# V1_pwr_sply_noNegSply_sch.net
KiCad netlist of a schematic drawn in Altium Designer
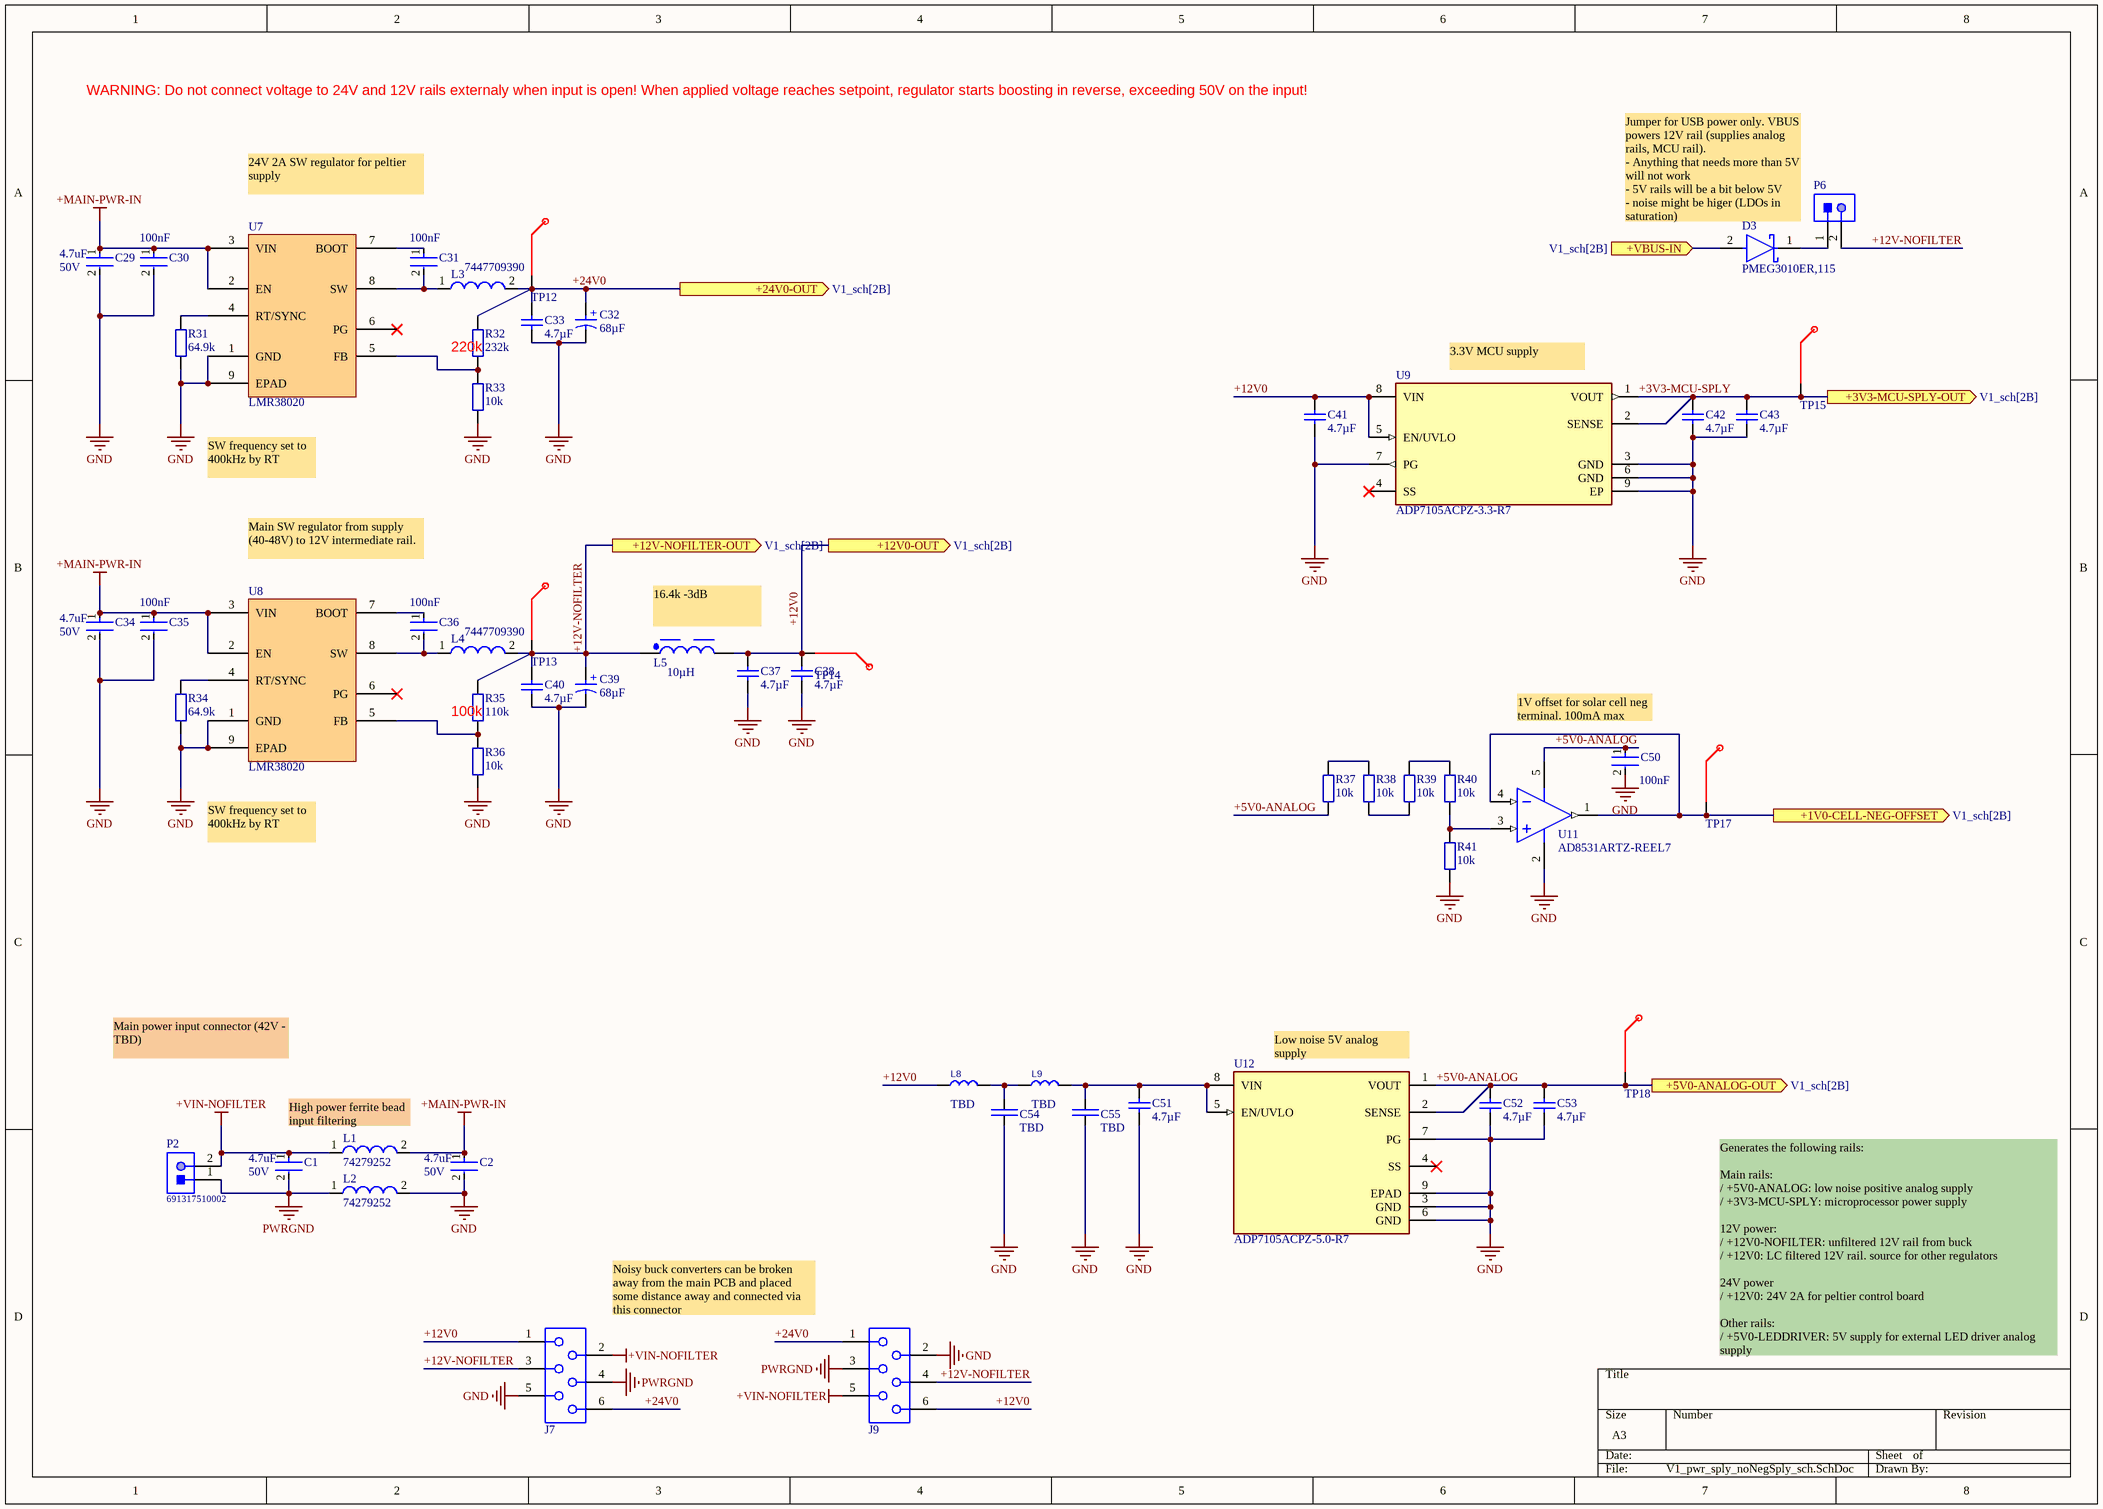
[diagram p0: V1_pwr_sply_noNegSply_sch.SchDoc]

(export (version "E")
  (design (tool "Eeschema 10.0.6"))
  (components
    (comp (ref "C1")
      (value "885012208094")
      (footprint "FP-885012208094-IPC_B")
      (description "CAP CER 4.7UF 50V X7R 1206")
      (fields
        (field (name "VOLTAGE RATING (DC)") "50V")
        (field (name "CAPACITANCE") "4.7uF")
        (field (name "TOLERANCE") "10%")
      )
      (libsource (lib "Altium Content Vault") (part "11868f565c42a9108669ba33697ecf6"))
    )
    (comp (ref "C2")
      (value "885012208094")
      (footprint "FP-885012208094-IPC_B")
      (description "CAP CER 4.7UF 50V X7R 1206")
      (fields
        (field (name "VOLTAGE RATING (DC)") "50V")
        (field (name "CAPACITANCE") "4.7uF")
        (field (name "TOLERANCE") "10%")
      )
      (libsource (lib "Altium Content Vault") (part "11868f565c42a9108669ba33697ecf6"))
    )
    (comp (ref "C29")
      (value "885012208094")
      (footprint "FP-885012208094-IPC_B")
      (description "CAP CER 4.7UF 50V X7R 1206")
      (fields
        (field (name "VOLTAGE RATING (DC)") "50V")
        (field (name "CAPACITANCE") "4.7uF")
        (field (name "TOLERANCE") "10%")
      )
      (libsource (lib "Altium Content Vault") (part "11868f565c42a9108669ba33697ecf6"))
    )
    (comp (ref "C30")
      (value "885012206095")
      (footprint "FP-885012206095-IPC_B")
      (description "CAP CER 0.1UF 50V X7R 0603")
      (fields (field (name "TOLERANCE") "10%") (field (name "CAPACITANCE") "100nF"))
      (libsource (lib "Altium Content Vault") (part "11868f565c42a9108669ba33697ecf6"))
    )
    (comp (ref "C31")
      (value "885012206095")
      (footprint "FP-885012206095-IPC_B")
      (description "CAP CER 0.1UF 50V X7R 0603")
      (fields (field (name "TOLERANCE") "10%") (field (name "CAPACITANCE") "100nF"))
      (libsource (lib "Altium Content Vault") (part "11868f565c42a9108669ba33697ecf6"))
    )
    (comp (ref "C32")
      (value "875115552001")
      (footprint "WCAP-PSHP_D8H8.7")
      (description "WCAP-PSHP Aluminum Polymer Capacitor, V-Chip, SMT, D8 x H8.7mm, 68µF, 25V")
      (fields (field (name "MANUFACTURER") "Wurth Elektronik") (field (name "CAPACITANCE") "68µF"))
      (libsource (lib "Altium_WCAP-PSHP (rev22c)") (part "875115552001"))
    )
    (comp (ref "C33")
      (value "885012107018")
      (footprint "WCAP-CSGP_0805_L2W1.25H1.25")
      (description "WCAP-CSGP Multilayer Ceramic Chip Capacitor, General Purpose, size 0805, X5R, 4.7µF, 25VDC")
      (fields (field (name "MANUFACTURER") "Wurth Elektronik") (field (name "CAPACITANCE") "4.7µF"))
      (libsource (lib "Altium_WCAP-CSGP (rev22f)") (part "885012107018"))
    )
    (comp (ref "C34")
      (value "885012208094")
      (footprint "FP-885012208094-IPC_B")
      (description "CAP CER 4.7UF 50V X7R 1206")
      (fields
        (field (name "VOLTAGE RATING (DC)") "50V")
        (field (name "CAPACITANCE") "4.7uF")
        (field (name "TOLERANCE") "10%")
      )
      (libsource (lib "Altium Content Vault") (part "11868f565c42a9108669ba33697ecf6"))
    )
    (comp (ref "C35")
      (value "885012206095")
      (footprint "FP-885012206095-IPC_B")
      (description "CAP CER 0.1UF 50V X7R 0603")
      (fields (field (name "TOLERANCE") "10%") (field (name "CAPACITANCE") "100nF"))
      (libsource (lib "Altium Content Vault") (part "11868f565c42a9108669ba33697ecf6"))
    )
    (comp (ref "C36")
      (value "885012206095")
      (footprint "FP-885012206095-IPC_B")
      (description "CAP CER 0.1UF 50V X7R 0603")
      (fields (field (name "TOLERANCE") "10%") (field (name "CAPACITANCE") "100nF"))
      (libsource (lib "Altium Content Vault") (part "11868f565c42a9108669ba33697ecf6"))
    )
    (comp (ref "C37")
      (value "885012107018")
      (footprint "WCAP-CSGP_0805_L2W1.25H1.25")
      (description "WCAP-CSGP Multilayer Ceramic Chip Capacitor, General Purpose, size 0805, X5R, 4.7µF, 25VDC")
      (fields (field (name "MANUFACTURER") "Wurth Elektronik") (field (name "CAPACITANCE") "4.7µF"))
      (libsource (lib "Altium_WCAP-CSGP (rev22f)") (part "885012107018"))
    )
    (comp (ref "C38")
      (value "885012107018")
      (footprint "WCAP-CSGP_0805_L2W1.25H1.25")
      (description "WCAP-CSGP Multilayer Ceramic Chip Capacitor, General Purpose, size 0805, X5R, 4.7µF, 25VDC")
      (fields (field (name "MANUFACTURER") "Wurth Elektronik") (field (name "CAPACITANCE") "4.7µF"))
      (libsource (lib "Altium_WCAP-CSGP (rev22f)") (part "885012107018"))
    )
    (comp (ref "C39")
      (value "875115552001")
      (footprint "WCAP-PSHP_D8H8.7")
      (description "WCAP-PSHP Aluminum Polymer Capacitor, V-Chip, SMT, D8 x H8.7mm, 68µF, 25V")
      (fields (field (name "MANUFACTURER") "Wurth Elektronik") (field (name "CAPACITANCE") "68µF"))
      (libsource (lib "Altium_WCAP-PSHP (rev22c)") (part "875115552001"))
    )
    (comp (ref "C40")
      (value "885012107018")
      (footprint "WCAP-CSGP_0805_L2W1.25H1.25")
      (description "WCAP-CSGP Multilayer Ceramic Chip Capacitor, General Purpose, size 0805, X5R, 4.7µF, 25VDC")
      (fields (field (name "MANUFACTURER") "Wurth Elektronik") (field (name "CAPACITANCE") "4.7µF"))
      (libsource (lib "Altium_WCAP-CSGP (rev22f)") (part "885012107018"))
    )
    (comp (ref "C41")
      (value "885012107018")
      (footprint "WCAP-CSGP_0805_L2W1.25H1.25")
      (description "WCAP-CSGP Multilayer Ceramic Chip Capacitor, General Purpose, size 0805, X5R, 4.7µF, 25VDC")
      (fields (field (name "MANUFACTURER") "Wurth Elektronik") (field (name "CAPACITANCE") "4.7µF"))
      (libsource (lib "Altium_WCAP-CSGP (rev22f)") (part "885012107018"))
    )
    (comp (ref "C42")
      (value "885012107018")
      (footprint "WCAP-CSGP_0805_L2W1.25H1.25")
      (description "WCAP-CSGP Multilayer Ceramic Chip Capacitor, General Purpose, size 0805, X5R, 4.7µF, 25VDC")
      (fields (field (name "MANUFACTURER") "Wurth Elektronik") (field (name "CAPACITANCE") "4.7µF"))
      (libsource (lib "Altium_WCAP-CSGP (rev22f)") (part "885012107018"))
    )
    (comp (ref "C43")
      (value "885012107018")
      (footprint "WCAP-CSGP_0805_L2W1.25H1.25")
      (description "WCAP-CSGP Multilayer Ceramic Chip Capacitor, General Purpose, size 0805, X5R, 4.7µF, 25VDC")
      (fields (field (name "MANUFACTURER") "Wurth Elektronik") (field (name "CAPACITANCE") "4.7µF"))
      (libsource (lib "Altium_WCAP-CSGP (rev22f)") (part "885012107018"))
    )
    (comp (ref "C50")
      (value "885012206095")
      (footprint "FP-885012206095-IPC_B")
      (description "CAP CER 0.1UF 50V X7R 0603")
      (fields (field (name "TOLERANCE") "10%") (field (name "CAPACITANCE") "100nF"))
      (libsource (lib "Altium Content Vault") (part "11868f565c42a9108669ba33697ecf6"))
    )
    (comp (ref "C51")
      (value "885012107018")
      (footprint "WCAP-CSGP_0805_L2W1.25H1.25")
      (description "WCAP-CSGP Multilayer Ceramic Chip Capacitor, General Purpose, size 0805, X5R, 4.7µF, 25VDC")
      (fields (field (name "MANUFACTURER") "Wurth Elektronik") (field (name "CAPACITANCE") "4.7µF"))
      (libsource (lib "Altium_WCAP-CSGP (rev22f)") (part "885012107018"))
    )
    (comp (ref "C52")
      (value "885012107018")
      (footprint "WCAP-CSGP_0805_L2W1.25H1.25")
      (description "WCAP-CSGP Multilayer Ceramic Chip Capacitor, General Purpose, size 0805, X5R, 4.7µF, 25VDC")
      (fields (field (name "MANUFACTURER") "Wurth Elektronik") (field (name "CAPACITANCE") "4.7µF"))
      (libsource (lib "Altium_WCAP-CSGP (rev22f)") (part "885012107018"))
    )
    (comp (ref "C53")
      (value "885012107018")
      (footprint "WCAP-CSGP_0805_L2W1.25H1.25")
      (description "WCAP-CSGP Multilayer Ceramic Chip Capacitor, General Purpose, size 0805, X5R, 4.7µF, 25VDC")
      (fields (field (name "MANUFACTURER") "Wurth Elektronik") (field (name "CAPACITANCE") "4.7µF"))
      (libsource (lib "Altium_WCAP-CSGP (rev22f)") (part "885012107018"))
    )
    (comp (ref "C54")
      (value "TBD")
      (footprint "Passives:FPR_0603_C_R0")
      (description "Capacitor - generic SMD")
      (fields (field (name "Comment") "PN_C0603_TBD"))
      (libsource (lib "Passives") (part "C"))
    )
    (comp (ref "C55")
      (value "TBD")
      (footprint "Passives:FPR_0603_C_R0")
      (description "Capacitor - generic SMD")
      (fields (field (name "Comment") "PN_C0603_TBD"))
      (libsource (lib "Passives") (part "C"))
    )
    (comp (ref "D3")
      (value "PMEG3010ER,115")
      (footprint "FP-SOD123W-MFG")
      (description "DIODE SCHOTTKY 30V 1A CFP3")
      (libsource (lib "Altium Content Vault") (part "1d6ec82d83fb6aee721767c19dac4b9"))
    )
    (comp (ref "J7")
      (value "690368190672")
      (footprint "690368190672")
      (description "WR-MM Mini Module Connector, Female, THT, with Latch & Polarization, Angled, pitch 2.54mm, 6p")
      (fields (field (name "MANUFACTURER") "Wurth Elektronik"))
      (libsource (lib "Altium_WR-MM (rev22a)") (part "690368190672"))
    )
    (comp (ref "J9")
      (value "690368190672")
      (footprint "690368190672")
      (description "WR-MM Mini Module Connector, Female, THT, with Latch & Polarization, Angled, pitch 2.54mm, 6p")
      (fields (field (name "MANUFACTURER") "Wurth Elektronik"))
      (libsource (lib "Altium_WR-MM (rev22a)") (part "690368190672"))
    )
    (comp (ref "L1")
      (value "74279252")
      (footprint "SMD-1812")
      (description "SMD EMI Suppression Ferrite Bead WE-CBF, Z = 680 Ohm")
      (libsource (lib "Altium Content Vault") (part "PAS-IND-INDUCTOR-2"))
    )
    (comp (ref "L2")
      (value "74279252")
      (footprint "SMD-1812")
      (description "SMD EMI Suppression Ferrite Bead WE-CBF, Z = 680 Ohm")
      (libsource (lib "Altium Content Vault") (part "PAS-IND-INDUCTOR-2"))
    )
    (comp (ref "L3")
      (value "7447709390")
      (footprint "WE-PD-XXL")
      (description "SMD-Shielded Power Inductor WE-PD, L = 39.0 µH")
      (libsource (lib "Altium Content Vault") (part "PAS-IND-INDUCTOR-2"))
    )
    (comp (ref "L4")
      (value "7447709390")
      (footprint "WE-PD-XXL")
      (description "SMD-Shielded Power Inductor WE-PD, L = 39.0 µH")
      (libsource (lib "Altium Content Vault") (part "PAS-IND-INDUCTOR-2"))
    )
    (comp (ref "L5")
      (value "74439346100")
      (footprint "WE-XHMI_6060_L6.65W6.45H5.8")
      (description "WE-XHMI SMT Power Inductor, size 6060, 10µH, 5A, 26.5mΩ")
      (fields (field (name "MANUFACTURER") "Wurth Elektronik") (field (name "INDUCTANCE") "10µH"))
      (libsource (lib "Altium_WE-XHMI (rev22e)") (part "74439346100"))
    )
    (comp (ref "L8")
      (value "TBD")
      (footprint "FPR_1216_R_R0")
      (description "Inductor - generic SMD")
      (fields (field (name "Comment") "L-TBD"))
      (libsource (lib "Passives") (part "L"))
    )
    (comp (ref "L9")
      (value "TBD")
      (footprint "FPR_1216_R_R0")
      (description "Inductor - generic SMD")
      (fields (field (name "Comment") "L-TBD"))
      (libsource (lib "Passives") (part "L"))
    )
    (comp (ref "P2")
      (value "691317510002")
      (footprint "691317510002")
      (description "Serie 3175 - 5.08mm Close Horizontal PCB Header with Flages WR-TBL, 2 pin")
      (fields (field (name "MANUFACTURER") "Wurth Elektronik") (field (name "PUBLISHER") "WurthElektronik"))
      (libsource (lib "") (part "WE-CN-1P-M-R2_1"))
    )
    (comp (ref "P6")
      (value "61300211121")
      (footprint "61300211121")
      (description "THT Vertical Pin Header WR-PHD, Pitch 2.54 mm, Single Row, 2 pins")
      (fields (field (name "MANUFACTURER") "Wurth Elektronik") (field (name "PUBLISHER") "WurthElektronik"))
      (libsource (lib "Altium Content Vault") (part "WE-CN-1P-M-R2"))
    )
    (comp (ref "R31")
      (value "64.9k")
      (footprint "Passives:FPR_0603_R_R0")
      (description "Resistor - generic SMD")
      (fields (field (name "Comment") "PN_R0603_64k9"))
      (libsource (lib "Passives") (part "R"))
    )
    (comp (ref "R32")
      (value "232k")
      (footprint "Passives:FPR_0603_R_R0")
      (description "Resistor - generic SMD")
      (fields (field (name "Comment") "PN_R0603_232k"))
      (libsource (lib "Passives") (part "R"))
    )
    (comp (ref "R33")
      (value "10k")
      (footprint "Passives:FPR_0603_R_R0")
      (description "Resistor - generic SMD")
      (fields (field (name "Comment") "PN_R0603_10k"))
      (libsource (lib "Passives") (part "R"))
    )
    (comp (ref "R34")
      (value "64.9k")
      (footprint "Passives:FPR_0603_R_R0")
      (description "Resistor - generic SMD")
      (fields (field (name "Comment") "PN_R0603_64k9"))
      (libsource (lib "Passives") (part "R"))
    )
    (comp (ref "R35")
      (value "110k")
      (footprint "Passives:FPR_0603_R_R0")
      (description "Resistor - generic SMD")
      (fields (field (name "Comment") "PN_R0603_110k"))
      (libsource (lib "Passives") (part "R"))
    )
    (comp (ref "R36")
      (value "10k")
      (footprint "Passives:FPR_0603_R_R0")
      (description "Resistor - generic SMD")
      (fields (field (name "Comment") "PN_R0603_10k"))
      (libsource (lib "Passives") (part "R"))
    )
    (comp (ref "R37")
      (value "10k")
      (footprint "Passives:FPR_0603_R_R0")
      (description "Resistor - generic SMD")
      (fields (field (name "Comment") "PN_R0603_10k"))
      (libsource (lib "Passives") (part "R"))
    )
    (comp (ref "R38")
      (value "10k")
      (footprint "Passives:FPR_0603_R_R0")
      (description "Resistor - generic SMD")
      (fields (field (name "Comment") "PN_R0603_10k"))
      (libsource (lib "Passives") (part "R"))
    )
    (comp (ref "R39")
      (value "10k")
      (footprint "Passives:FPR_0603_R_R0")
      (description "Resistor - generic SMD")
      (fields (field (name "Comment") "PN_R0603_10k"))
      (libsource (lib "Passives") (part "R"))
    )
    (comp (ref "R40")
      (value "10k")
      (footprint "Passives:FPR_0603_R_R0")
      (description "Resistor - generic SMD")
      (fields (field (name "Comment") "PN_R0603_10k"))
      (libsource (lib "Passives") (part "R"))
    )
    (comp (ref "R41")
      (value "10k")
      (footprint "Passives:FPR_0603_R_R0")
      (description "Resistor - generic SMD")
      (fields (field (name "Comment") "PN_R0603_10k"))
      (libsource (lib "Passives") (part "R"))
    )
    (comp (ref "TP12")
      (value "Test Point")
      (footprint "Test Point 1.5mm SMD")
      (libsource (lib "planinsekLib_sch") (part "Test Point"))
    )
    (comp (ref "TP13")
      (value "Test Point")
      (footprint "Test Point 1.5mm SMD")
      (libsource (lib "planinsekLib_sch") (part "Test Point"))
    )
    (comp (ref "TP14")
      (value "Test Point")
      (footprint "Test Point 1.5mm SMD")
      (libsource (lib "planinsekLib_sch") (part "Test Point"))
    )
    (comp (ref "TP15")
      (value "Test Point")
      (footprint "Test Point 1.5mm SMD")
      (libsource (lib "planinsekLib_sch") (part "Test Point"))
    )
    (comp (ref "TP17")
      (value "Test Point")
      (footprint "Test Point 1.5mm SMD")
      (libsource (lib "planinsekLib_sch") (part "Test Point"))
    )
    (comp (ref "TP18")
      (value "Test Point")
      (footprint "Test Point 1.5mm SMD")
      (libsource (lib "planinsekLib_sch") (part "Test Point"))
    )
    (comp (ref "U7")
      (value "LMR38020")
      (footprint "LMR38020-footprint")
      (description "LMR38020 SIMPLE SWITCHER® 4.2-V to 80-V, 2-A Synchronous Buck Converter with 40-µA IQ")
      (libsource (lib "planinsekLib_sch") (part "LMR38020"))
    )
    (comp (ref "U8")
      (value "LMR38020")
      (footprint "LMR38020-footprint")
      (description "LMR38020 SIMPLE SWITCHER® 4.2-V to 80-V, 2-A Synchronous Buck Converter with 40-µA IQ")
      (libsource (lib "planinsekLib_sch") (part "LMR38020"))
    )
    (comp (ref "U9")
      (value "ADP7105ACPZ-3.3-R7")
      (footprint "FP-CP-8-5-IPC_C")
      (description "IC REG LINEAR 3.3V 500MA 8LFCSP")
      (libsource (lib "Altium Content Vault") (part "80572691877daf598b7f400c479e799"))
    )
    (comp (ref "U11")
      (value "AD8531ARTZ-REEL7")
      (footprint "ADI-RJ-5_M")
      (fields (field (name "MANUFACTURER") "Analog Devices") (field (name "GENERIC PART NUMBER") "AD8531"))
      (libsource (lib "Altium Content Vault") (part "ADI-AD85XX-5"))
    )
    (comp (ref "U12")
      (value "ADP7105ACPZ-5.0-R7")
      (footprint "FP-CP-8-5-IPC_C")
      (description "IC REG LINEAR 5V 500MA 8LFCSP")
      (libsource (lib "Altium Content Vault") (part "3afc8f7b7a475b796d1e7b3a9bf20b9"))
    )
  )
  (nets
    (net (code "1") (name "+MAIN-PWR-IN") (class "Default")
      (node (ref "C2") (pin "1") (pinfunction "1_1") (pintype "passive"))
      (node (ref "C29") (pin "1") (pinfunction "1_1") (pintype "passive"))
      (node (ref "C30") (pin "1") (pinfunction "1_1") (pintype "passive"))
      (node (ref "C34") (pin "1") (pinfunction "1_1") (pintype "passive"))
      (node (ref "C35") (pin "1") (pinfunction "1_1") (pintype "passive"))
      (node (ref "L1") (pin "2") (pinfunction "2_2") (pintype "passive"))
      (node (ref "U7") (pin "2") (pinfunction "EN_2") (pintype "passive"))
      (node (ref "U7") (pin "3") (pinfunction "VIN_3") (pintype "passive"))
      (node (ref "U8") (pin "2") (pinfunction "EN_2") (pintype "passive"))
      (node (ref "U8") (pin "3") (pinfunction "VIN_3") (pintype "passive"))
    )
    (net (code "2") (name "+VIN-NOFILTER") (class "Default")
      (node (ref "C1") (pin "1") (pinfunction "1_1") (pintype "passive"))
      (node (ref "J7") (pin "2") (pinfunction "2_2") (pintype "passive"))
      (node (ref "J9") (pin "5") (pinfunction "5_5") (pintype "passive"))
      (node (ref "L1") (pin "1") (pinfunction "1_1") (pintype "passive"))
      (node (ref "P2") (pin "2") (pinfunction "2_2") (pintype "passive"))
    )
    (net (code "3") (name "/+1V0-CELL-NEG-OFFSET") (class "Default")
      (node (ref "TP17") (pin "1") (pintype "passive"))
      (node (ref "U11") (pin "1") (pinfunction "OUT_A_1") (pintype "output"))
      (node (ref "U11") (pin "4") (pinfunction "-IN_A_4") (pintype "input"))
    )
    (net (code "4") (name "/+3V3-MCU-SPLY") (class "Default")
      (node (ref "C42") (pin "2") (pinfunction "2_2") (pintype "passive"))
      (node (ref "C43") (pin "2") (pinfunction "2_2") (pintype "passive"))
      (node (ref "TP15") (pin "1") (pintype "passive"))
      (node (ref "U9") (pin "1") (pinfunction "VOUT_1") (pintype "output"))
      (node (ref "U9") (pin "2") (pinfunction "SENSE_2") (pintype "passive"))
    )
    (net (code "5") (name "/+5V0-ANALOG") (class "Default")
      (node (ref "C50") (pin "1") (pinfunction "1_1") (pintype "passive"))
      (node (ref "C52") (pin "2") (pinfunction "2_2") (pintype "passive"))
      (node (ref "C53") (pin "2") (pinfunction "2_2") (pintype "passive"))
      (node (ref "R37") (pin "1") (pinfunction "1_1") (pintype "passive"))
      (node (ref "TP18") (pin "1") (pintype "passive"))
      (node (ref "U11") (pin "5") (pinfunction "+V_5") (pintype "power_in"))
      (node (ref "U12") (pin "1") (pinfunction "VOUT_1") (pintype "power_in"))
      (node (ref "U12") (pin "2") (pinfunction "SENSE_2") (pintype "power_in"))
    )
    (net (code "6") (name "/+12V-NOFILTER") (class "Default")
      (node (ref "C39") (pin "1") (pinfunction "P_1") (pintype "passive"))
      (node (ref "C40") (pin "2") (pinfunction "2_2") (pintype "passive"))
      (node (ref "J7") (pin "3") (pinfunction "3_3") (pintype "passive"))
      (node (ref "J9") (pin "4") (pinfunction "4_4") (pintype "passive"))
      (node (ref "L4") (pin "2") (pinfunction "2_2") (pintype "passive"))
      (node (ref "L5") (pin "1") (pinfunction "1_1") (pintype "passive"))
      (node (ref "P6") (pin "2") (pinfunction "2_2") (pintype "passive"))
      (node (ref "R35") (pin "2") (pinfunction "2_2") (pintype "passive"))
      (node (ref "TP13") (pin "1") (pintype "passive"))
    )
    (net (code "7") (name "/+12V0") (class "Default")
      (node (ref "C37") (pin "2") (pinfunction "2_2") (pintype "passive"))
      (node (ref "C38") (pin "2") (pinfunction "2_2") (pintype "passive"))
      (node (ref "C41") (pin "2") (pinfunction "2_2") (pintype "passive"))
      (node (ref "J7") (pin "1") (pinfunction "1_1") (pintype "passive"))
      (node (ref "J9") (pin "6") (pinfunction "6_6") (pintype "passive"))
      (node (ref "L5") (pin "2") (pinfunction "2_2") (pintype "passive"))
      (node (ref "L8") (pin "1") (pintype "passive"))
      (node (ref "TP14") (pin "1") (pintype "passive"))
      (node (ref "U9") (pin "5") (pinfunction "EN/UVLO_5") (pintype "input"))
      (node (ref "U9") (pin "8") (pinfunction "VIN_8") (pintype "power_in"))
    )
    (net (code "8") (name "/+24V0") (class "Default")
      (node (ref "C32") (pin "1") (pinfunction "P_1") (pintype "passive"))
      (node (ref "C33") (pin "2") (pinfunction "2_2") (pintype "passive"))
      (node (ref "J7") (pin "6") (pinfunction "6_6") (pintype "passive"))
      (node (ref "J9") (pin "1") (pinfunction "1_1") (pintype "passive"))
      (node (ref "L3") (pin "2") (pinfunction "2_2") (pintype "passive"))
      (node (ref "R32") (pin "2") (pinfunction "2_2") (pintype "passive"))
      (node (ref "TP12") (pin "1") (pintype "passive"))
    )
    (net (code "9") (name "/+VBUS-IN") (class "Default")
      (node (ref "D3") (pin "2") (pinfunction "A_2") (pintype "passive"))
    )
    (net (code "10") (name "GND") (class "Default")
      (node (ref "C2") (pin "2") (pinfunction "2_2") (pintype "passive"))
      (node (ref "C29") (pin "2") (pinfunction "2_2") (pintype "passive"))
      (node (ref "C30") (pin "2") (pinfunction "2_2") (pintype "passive"))
      (node (ref "C32") (pin "2") (pinfunction "N_2") (pintype "passive"))
      (node (ref "C33") (pin "1") (pinfunction "1_1") (pintype "passive"))
      (node (ref "C34") (pin "2") (pinfunction "2_2") (pintype "passive"))
      (node (ref "C35") (pin "2") (pinfunction "2_2") (pintype "passive"))
      (node (ref "C37") (pin "1") (pinfunction "1_1") (pintype "passive"))
      (node (ref "C38") (pin "1") (pinfunction "1_1") (pintype "passive"))
      (node (ref "C39") (pin "2") (pinfunction "N_2") (pintype "passive"))
      (node (ref "C40") (pin "1") (pinfunction "1_1") (pintype "passive"))
      (node (ref "C41") (pin "1") (pinfunction "1_1") (pintype "passive"))
      (node (ref "C42") (pin "1") (pinfunction "1_1") (pintype "passive"))
      (node (ref "C43") (pin "1") (pinfunction "1_1") (pintype "passive"))
      (node (ref "C50") (pin "2") (pinfunction "2_2") (pintype "passive"))
      (node (ref "C51") (pin "1") (pinfunction "1_1") (pintype "passive"))
      (node (ref "C52") (pin "1") (pinfunction "1_1") (pintype "passive"))
      (node (ref "C53") (pin "1") (pinfunction "1_1") (pintype "passive"))
      (node (ref "C54") (pin "1") (pinfunction "1_1") (pintype "passive"))
      (node (ref "C55") (pin "1") (pinfunction "1_1") (pintype "passive"))
      (node (ref "J7") (pin "5") (pinfunction "5_5") (pintype "passive"))
      (node (ref "J9") (pin "2") (pinfunction "2_2") (pintype "passive"))
      (node (ref "L2") (pin "2") (pinfunction "2_2") (pintype "passive"))
      (node (ref "R31") (pin "1") (pinfunction "1_1") (pintype "passive"))
      (node (ref "R33") (pin "1") (pinfunction "1_1") (pintype "passive"))
      (node (ref "R34") (pin "1") (pinfunction "1_1") (pintype "passive"))
      (node (ref "R36") (pin "1") (pinfunction "1_1") (pintype "passive"))
      (node (ref "R41") (pin "1") (pinfunction "1_1") (pintype "passive"))
      (node (ref "U11") (pin "2") (pinfunction "-V_2") (pintype "power_in"))
      (node (ref "U12") (pin "3") (pinfunction "GND_3") (pintype "power_in"))
      (node (ref "U12") (pin "6") (pinfunction "GND_6") (pintype "power_in"))
      (node (ref "U12") (pin "7") (pinfunction "PG_7") (pintype "open_collector"))
      (node (ref "U12") (pin "9") (pinfunction "EPAD_9") (pintype "power_in"))
      (node (ref "U7") (pin "1") (pinfunction "GND_1") (pintype "passive"))
      (node (ref "U7") (pin "9") (pinfunction "EPAD_9") (pintype "passive"))
      (node (ref "U8") (pin "1") (pinfunction "GND_1") (pintype "passive"))
      (node (ref "U8") (pin "9") (pinfunction "EPAD_9") (pintype "passive"))
      (node (ref "U9") (pin "3") (pinfunction "GND_3") (pintype "power_in"))
      (node (ref "U9") (pin "6") (pinfunction "GND_6") (pintype "power_in"))
      (node (ref "U9") (pin "7") (pinfunction "PG_7") (pintype "output"))
      (node (ref "U9") (pin "9") (pinfunction "EP_9") (pintype "passive"))
    )
    (net (code "11") (name "Net-(C54-Pad2)") (class "Default")
      (node (ref "C54") (pin "2") (pinfunction "2_2") (pintype "passive"))
      (node (ref "L8") (pin "2") (pintype "passive"))
      (node (ref "L9") (pin "1") (pintype "passive"))
    )
    (net (code "12") (name "Net-(D3-C)") (class "Default")
      (node (ref "D3") (pin "1") (pinfunction "C_1") (pintype "passive"))
      (node (ref "P6") (pin "1") (pinfunction "1_1") (pintype "passive"))
    )
    (net (code "13") (name "Net-(R37-Pad2)") (class "Default")
      (node (ref "R37") (pin "2") (pinfunction "2_2") (pintype "passive"))
      (node (ref "R38") (pin "2") (pinfunction "2_2") (pintype "passive"))
    )
    (net (code "14") (name "Net-(R38-Pad1)") (class "Default")
      (node (ref "R38") (pin "1") (pinfunction "1_1") (pintype "passive"))
      (node (ref "R39") (pin "1") (pinfunction "1_1") (pintype "passive"))
    )
    (net (code "15") (name "Net-(R39-Pad2)") (class "Default")
      (node (ref "R39") (pin "2") (pinfunction "2_2") (pintype "passive"))
      (node (ref "R40") (pin "2") (pinfunction "2_2") (pintype "passive"))
    )
    (net (code "16") (name "Net-(U7-BOOT)") (class "Default")
      (node (ref "C31") (pin "1") (pinfunction "1_1") (pintype "passive"))
      (node (ref "U7") (pin "7") (pinfunction "BOOT_7") (pintype "passive"))
    )
    (net (code "17") (name "Net-(U7-FB)") (class "Default")
      (node (ref "R32") (pin "1") (pinfunction "1_1") (pintype "passive"))
      (node (ref "R33") (pin "2") (pinfunction "2_2") (pintype "passive"))
      (node (ref "U7") (pin "5") (pinfunction "FB_5") (pintype "passive"))
    )
    (net (code "18") (name "Net-(U7-RT{slash}SYNC)") (class "Default")
      (node (ref "R31") (pin "2") (pinfunction "2_2") (pintype "passive"))
      (node (ref "U7") (pin "4") (pinfunction "RT/SYNC_4") (pintype "passive"))
    )
    (net (code "19") (name "Net-(U7-SW)") (class "Default")
      (node (ref "C31") (pin "2") (pinfunction "2_2") (pintype "passive"))
      (node (ref "L3") (pin "1") (pinfunction "1_1") (pintype "passive"))
      (node (ref "U7") (pin "8") (pinfunction "SW_8") (pintype "passive"))
    )
    (net (code "20") (name "Net-(U8-BOOT)") (class "Default")
      (node (ref "C36") (pin "1") (pinfunction "1_1") (pintype "passive"))
      (node (ref "U8") (pin "7") (pinfunction "BOOT_7") (pintype "passive"))
    )
    (net (code "21") (name "Net-(U8-FB)") (class "Default")
      (node (ref "R35") (pin "1") (pinfunction "1_1") (pintype "passive"))
      (node (ref "R36") (pin "2") (pinfunction "2_2") (pintype "passive"))
      (node (ref "U8") (pin "5") (pinfunction "FB_5") (pintype "passive"))
    )
    (net (code "22") (name "Net-(U8-RT{slash}SYNC)") (class "Default")
      (node (ref "R34") (pin "2") (pinfunction "2_2") (pintype "passive"))
      (node (ref "U8") (pin "4") (pinfunction "RT/SYNC_4") (pintype "passive"))
    )
    (net (code "23") (name "Net-(U8-SW)") (class "Default")
      (node (ref "C36") (pin "2") (pinfunction "2_2") (pintype "passive"))
      (node (ref "L4") (pin "1") (pinfunction "1_1") (pintype "passive"))
      (node (ref "U8") (pin "8") (pinfunction "SW_8") (pintype "passive"))
    )
    (net (code "24") (name "Net-(U11-+IN_A)") (class "Default")
      (node (ref "R40") (pin "1") (pinfunction "1_1") (pintype "passive"))
      (node (ref "R41") (pin "2") (pinfunction "2_2") (pintype "passive"))
      (node (ref "U11") (pin "3") (pinfunction "+IN_A_3") (pintype "input"))
    )
    (net (code "25") (name "Net-(U12-EN{slash}UVLO)") (class "Default")
      (node (ref "C51") (pin "2") (pinfunction "2_2") (pintype "passive"))
      (node (ref "C55") (pin "2") (pinfunction "2_2") (pintype "passive"))
      (node (ref "L9") (pin "2") (pintype "passive"))
      (node (ref "U12") (pin "5") (pinfunction "EN/UVLO_5") (pintype "input"))
      (node (ref "U12") (pin "8") (pinfunction "VIN_8") (pintype "power_in"))
    )
    (net (code "26") (name "PWRGND") (class "Default")
      (node (ref "C1") (pin "2") (pinfunction "2_2") (pintype "passive"))
      (node (ref "J7") (pin "4") (pinfunction "4_4") (pintype "passive"))
      (node (ref "J9") (pin "3") (pinfunction "3_3") (pintype "passive"))
      (node (ref "L2") (pin "1") (pinfunction "1_1") (pintype "passive"))
      (node (ref "P2") (pin "1") (pinfunction "1_1") (pintype "passive"))
    )
    (net (code "27") (name "unconnected-(U7-PG-Pad6)") (class "Default")
      (node (ref "U7") (pin "6") (pinfunction "PG_6") (pintype "passive+no_connect"))
    )
    (net (code "28") (name "unconnected-(U8-PG-Pad6)") (class "Default")
      (node (ref "U8") (pin "6") (pinfunction "PG_6") (pintype "passive+no_connect"))
    )
    (net (code "29") (name "unconnected-(U9-SS-Pad4)") (class "Default")
      (node (ref "U9") (pin "4") (pinfunction "SS_4") (pintype "passive+no_connect"))
    )
    (net (code "30") (name "unconnected-(U12-SS-Pad4)") (class "Default")
      (node (ref "U12") (pin "4") (pinfunction "SS_4") (pintype "passive+no_connect"))
    )
  )
)
